# ChessMechPCB2.net
KiCad netlist of a schematic drawn in EAGLE
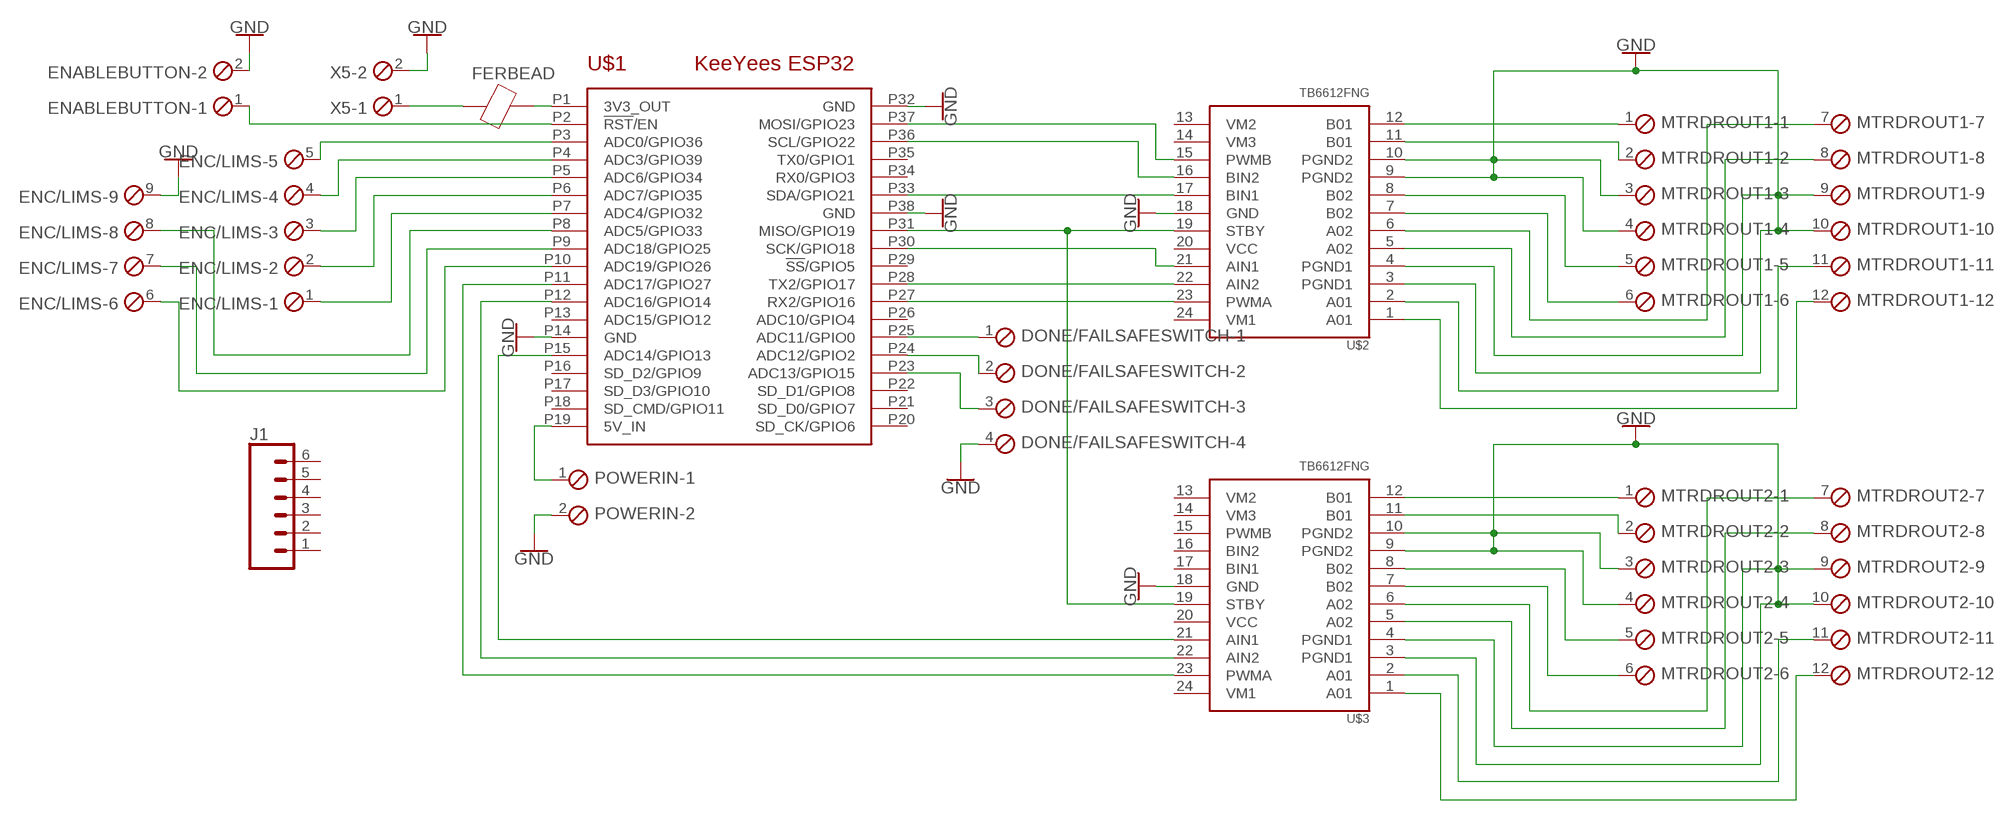
[diagram p0: schematic, sheet 1]

(export (version "E")
  (design (tool "Eeschema 10.0.6"))
  (components
    (comp (ref "DONE/FAILSAFESWITCH")
      (value "SCREWTERM_4P_254")
      (footprint "eagle-import:4POL254")
      (libsource (lib "eagle-import") (part "SCREWTERM_4P_254"))
    )
    (comp (ref "ENABLEBUTTON")
      (value "SCREWTERM_2P_254")
      (footprint "eagle-import:2POL254")
      (libsource (lib "eagle-import") (part "SCREWTERM_2P_254"))
    )
    (comp (ref "ENC/LIMS")
      (value "SCREWTERM_9P_254")
      (footprint "eagle-import:9POL254")
      (libsource (lib "eagle-import") (part "SCREWTERM_9P_254"))
    )
    (comp (ref "FERBEAD")
      (value "BEAD0402")
      (footprint "eagle-import:0402")
      (libsource (lib "eagle-import") (part "BEAD0402"))
    )
    (comp (ref "J1")
      (value "CONN_06SILK_FEMALE_PTH")
      (footprint "eagle-import:1X06")
      (libsource (lib "eagle-import") (part "CONN_06SILK_FEMALE_PTH"))
    )
    (comp (ref "MTRDROUT1")
      (value "SCREWTERM_12P_254")
      (footprint "eagle-import:12POL254")
      (libsource (lib "eagle-import") (part "SCREWTERM_12P_254"))
    )
    (comp (ref "MTRDROUT2")
      (value "SCREWTERM_12P_254")
      (footprint "eagle-import:12POL254")
      (libsource (lib "eagle-import") (part "SCREWTERM_12P_254"))
    )
    (comp (ref "POWERIN")
      (value "SCREWTERM_2P_254")
      (footprint "eagle-import:2POL254")
      (libsource (lib "eagle-import") (part "SCREWTERM_2P_254"))
    )
    (comp (ref "U$1")
      (value "KEEYEES_ESP32")
      (footprint "eagle-import:KEEYEES_ESP32")
      (libsource (lib "eagle-import") (part "KEEYEES_ESP32"))
    )
    (comp (ref "U$2")
      (value "TB6612FNG")
      (footprint "eagle-import:SSOP24")
      (libsource (lib "eagle-import") (part "TB6612FNG"))
    )
    (comp (ref "U$3")
      (value "TB6612FNG")
      (footprint "eagle-import:SSOP24")
      (libsource (lib "eagle-import") (part "TB6612FNG"))
    )
    (comp (ref "X5")
      (value "SCREWTERM_2P_254")
      (footprint "eagle-import:2POL254")
      (libsource (lib "eagle-import") (part "SCREWTERM_2P_254"))
    )
  )
  (nets
    (net (code "1") (name "GND") (class "Default")
      (node (ref "DONE/FAILSAFESWITCH") (pin "4") (pinfunction "1_4") (pintype "passive"))
      (node (ref "ENABLEBUTTON") (pin "2") (pinfunction "1_2") (pintype "passive"))
      (node (ref "ENC/LIMS") (pin "9") (pinfunction "1_9") (pintype "passive"))
      (node (ref "MTRDROUT1") (pin "10") (pinfunction "1_10") (pintype "passive"))
      (node (ref "MTRDROUT1") (pin "3") (pinfunction "1_3") (pintype "passive"))
      (node (ref "MTRDROUT1") (pin "4") (pinfunction "1_4") (pintype "passive"))
      (node (ref "MTRDROUT1") (pin "9") (pinfunction "1_9") (pintype "passive"))
      (node (ref "MTRDROUT2") (pin "10") (pinfunction "1_10") (pintype "passive"))
      (node (ref "MTRDROUT2") (pin "3") (pinfunction "1_3") (pintype "passive"))
      (node (ref "MTRDROUT2") (pin "4") (pinfunction "1_4") (pintype "passive"))
      (node (ref "MTRDROUT2") (pin "9") (pinfunction "1_9") (pintype "passive"))
      (node (ref "POWERIN") (pin "2") (pinfunction "1_2") (pintype "passive"))
      (node (ref "U$1") (pin "P14") (pinfunction "GND_P14") (pintype "power_in"))
      (node (ref "U$1") (pin "P32") (pinfunction "GND_P32") (pintype "power_in"))
      (node (ref "U$1") (pin "P38") (pinfunction "GND_P38") (pintype "power_in"))
      (node (ref "U$2") (pin "10") (pinfunction "PGND2_10") (pintype "bidirectional"))
      (node (ref "U$2") (pin "18") (pinfunction "GND_18") (pintype "bidirectional"))
      (node (ref "U$2") (pin "3") (pinfunction "PGND1_3") (pintype "bidirectional"))
      (node (ref "U$2") (pin "4") (pinfunction "PGND1_4") (pintype "bidirectional"))
      (node (ref "U$2") (pin "9") (pinfunction "PGND2_9") (pintype "bidirectional"))
      (node (ref "U$3") (pin "10") (pinfunction "PGND2_10") (pintype "bidirectional"))
      (node (ref "U$3") (pin "18") (pinfunction "GND_18") (pintype "bidirectional"))
      (node (ref "U$3") (pin "3") (pinfunction "PGND1_3") (pintype "bidirectional"))
      (node (ref "U$3") (pin "4") (pinfunction "PGND1_4") (pintype "bidirectional"))
      (node (ref "U$3") (pin "9") (pinfunction "PGND2_9") (pintype "bidirectional"))
      (node (ref "X5") (pin "2") (pinfunction "1_2") (pintype "passive"))
    )
    (net (code "2") (name "Net-(DONE/FAILSAFESWITCHB-1)") (class "Default")
      (node (ref "DONE/FAILSAFESWITCH") (pin "2") (pinfunction "1_2") (pintype "passive"))
      (node (ref "U$1") (pin "P24") (pinfunction "ADC12/GPIO2_P24") (pintype "bidirectional"))
    )
    (net (code "3") (name "Net-(DONE/FAILSAFESWITCHC-1)") (class "Default")
      (node (ref "DONE/FAILSAFESWITCH") (pin "3") (pinfunction "1_3") (pintype "passive"))
      (node (ref "U$1") (pin "P23") (pinfunction "ADC13/GPIO15_P23") (pintype "bidirectional"))
    )
    (net (code "4") (name "Net-(ENC/LIMSB-1)") (class "Default")
      (node (ref "ENC/LIMS") (pin "2") (pinfunction "1_2") (pintype "passive"))
      (node (ref "U$1") (pin "P6") (pinfunction "ADC7/GPIO35_P6") (pintype "bidirectional"))
    )
    (net (code "5") (name "Net-(ENC/LIMSC-1)") (class "Default")
      (node (ref "ENC/LIMS") (pin "3") (pinfunction "1_3") (pintype "passive"))
      (node (ref "U$1") (pin "P5") (pinfunction "ADC6/GPIO34_P5") (pintype "bidirectional"))
    )
    (net (code "6") (name "Net-(ENC/LIMSD-1)") (class "Default")
      (node (ref "ENC/LIMS") (pin "4") (pinfunction "1_4") (pintype "passive"))
      (node (ref "U$1") (pin "P4") (pinfunction "ADC3/GPIO39_P4") (pintype "bidirectional"))
    )
    (net (code "7") (name "Net-(ENC/LIMSE-1)") (class "Default")
      (node (ref "ENC/LIMS") (pin "5") (pinfunction "1_5") (pintype "passive"))
      (node (ref "U$1") (pin "P3") (pinfunction "ADC0/GPIO36_P3") (pintype "bidirectional"))
    )
    (net (code "8") (name "Net-(ENC/LIMSF-1)") (class "Default")
      (node (ref "ENC/LIMS") (pin "6") (pinfunction "1_6") (pintype "passive"))
      (node (ref "U$1") (pin "P10") (pinfunction "ADC19/GPIO26_P10") (pintype "bidirectional"))
    )
    (net (code "9") (name "Net-(ENC/LIMSG-1)") (class "Default")
      (node (ref "ENC/LIMS") (pin "7") (pinfunction "1_7") (pintype "passive"))
      (node (ref "U$1") (pin "P9") (pinfunction "ADC18/GPIO25_P9") (pintype "bidirectional"))
    )
    (net (code "10") (name "Net-(ENC/LIMSH-1)") (class "Default")
      (node (ref "ENC/LIMS") (pin "8") (pinfunction "1_8") (pintype "passive"))
      (node (ref "U$1") (pin "P8") (pinfunction "ADC5/GPIO33_P8") (pintype "bidirectional"))
    )
    (net (code "11") (name "Net-(FERBEAD-Pad1)") (class "Default")
      (node (ref "FERBEAD") (pin "1") (pinfunction "1_1") (pintype "bidirectional"))
      (node (ref "X5") (pin "1") (pinfunction "1_1") (pintype "passive"))
    )
    (net (code "12") (name "Net-(MTRDROUT1-Pad1)") (class "Default")
      (node (ref "MTRDROUT1") (pin "1") (pinfunction "1_1") (pintype "passive"))
      (node (ref "U$2") (pin "12") (pinfunction "B01_12") (pintype "bidirectional"))
    )
    (net (code "13") (name "Net-(MTRDROUT1C-1)") (class "Default")
      (node (ref "MTRDROUT1") (pin "11") (pinfunction "1_11") (pintype "passive"))
      (node (ref "U$2") (pin "2") (pinfunction "A01_2") (pintype "bidirectional"))
    )
    (net (code "14") (name "Net-(MTRDROUT1D-1)") (class "Default")
      (node (ref "MTRDROUT1") (pin "12") (pinfunction "1_12") (pintype "passive"))
      (node (ref "U$2") (pin "1") (pinfunction "A01_1") (pintype "bidirectional"))
    )
    (net (code "15") (name "Net-(MTRDROUT1E-1)") (class "Default")
      (node (ref "MTRDROUT1") (pin "2") (pinfunction "1_2") (pintype "passive"))
      (node (ref "U$2") (pin "11") (pinfunction "B01_11") (pintype "bidirectional"))
    )
    (net (code "16") (name "Net-(MTRDROUT1H-1)") (class "Default")
      (node (ref "MTRDROUT1") (pin "5") (pinfunction "1_5") (pintype "passive"))
      (node (ref "U$2") (pin "8") (pinfunction "B02_8") (pintype "bidirectional"))
    )
    (net (code "17") (name "Net-(MTRDROUT1I-1)") (class "Default")
      (node (ref "MTRDROUT1") (pin "6") (pinfunction "1_6") (pintype "passive"))
      (node (ref "U$2") (pin "7") (pinfunction "B02_7") (pintype "bidirectional"))
    )
    (net (code "18") (name "Net-(MTRDROUT1J-1)") (class "Default")
      (node (ref "MTRDROUT1") (pin "7") (pinfunction "1_7") (pintype "passive"))
      (node (ref "U$2") (pin "6") (pinfunction "A02_6") (pintype "bidirectional"))
    )
    (net (code "19") (name "Net-(MTRDROUT1K-1)") (class "Default")
      (node (ref "MTRDROUT1") (pin "8") (pinfunction "1_8") (pintype "passive"))
      (node (ref "U$2") (pin "5") (pinfunction "A02_5") (pintype "bidirectional"))
    )
    (net (code "20") (name "Net-(MTRDROUT2-Pad1)") (class "Default")
      (node (ref "MTRDROUT2") (pin "1") (pinfunction "1_1") (pintype "passive"))
      (node (ref "U$3") (pin "12") (pinfunction "B01_12") (pintype "bidirectional"))
    )
    (net (code "21") (name "Net-(MTRDROUT2C-1)") (class "Default")
      (node (ref "MTRDROUT2") (pin "11") (pinfunction "1_11") (pintype "passive"))
      (node (ref "U$3") (pin "2") (pinfunction "A01_2") (pintype "bidirectional"))
    )
    (net (code "22") (name "Net-(MTRDROUT2D-1)") (class "Default")
      (node (ref "MTRDROUT2") (pin "12") (pinfunction "1_12") (pintype "passive"))
      (node (ref "U$3") (pin "1") (pinfunction "A01_1") (pintype "bidirectional"))
    )
    (net (code "23") (name "Net-(MTRDROUT2E-1)") (class "Default")
      (node (ref "MTRDROUT2") (pin "2") (pinfunction "1_2") (pintype "passive"))
      (node (ref "U$3") (pin "11") (pinfunction "B01_11") (pintype "bidirectional"))
    )
    (net (code "24") (name "Net-(MTRDROUT2H-1)") (class "Default")
      (node (ref "MTRDROUT2") (pin "5") (pinfunction "1_5") (pintype "passive"))
      (node (ref "U$3") (pin "8") (pinfunction "B02_8") (pintype "bidirectional"))
    )
    (net (code "25") (name "Net-(MTRDROUT2I-1)") (class "Default")
      (node (ref "MTRDROUT2") (pin "6") (pinfunction "1_6") (pintype "passive"))
      (node (ref "U$3") (pin "7") (pinfunction "B02_7") (pintype "bidirectional"))
    )
    (net (code "26") (name "Net-(MTRDROUT2J-1)") (class "Default")
      (node (ref "MTRDROUT2") (pin "7") (pinfunction "1_7") (pintype "passive"))
      (node (ref "U$3") (pin "6") (pinfunction "A02_6") (pintype "bidirectional"))
    )
    (net (code "27") (name "Net-(MTRDROUT2K-1)") (class "Default")
      (node (ref "MTRDROUT2") (pin "8") (pinfunction "1_8") (pintype "passive"))
      (node (ref "U$3") (pin "5") (pinfunction "A02_5") (pintype "bidirectional"))
    )
    (net (code "28") (name "Net-(U$1-3V3_OUT)") (class "Default")
      (node (ref "FERBEAD") (pin "2") (pinfunction "2_2") (pintype "bidirectional"))
      (node (ref "U$1") (pin "P1") (pinfunction "3V3_OUT_P1") (pintype "power_in"))
    )
    (net (code "29") (name "Net-(U$1-5V_IN)") (class "Default")
      (node (ref "POWERIN") (pin "1") (pinfunction "1_1") (pintype "passive"))
      (node (ref "U$1") (pin "P19") (pinfunction "5V_IN_P19") (pintype "power_in"))
    )
    (net (code "30") (name "Net-(U$1-ADC4{slash}GPIO32)") (class "Default")
      (node (ref "ENC/LIMS") (pin "1") (pinfunction "1_1") (pintype "passive"))
      (node (ref "U$1") (pin "P7") (pinfunction "ADC4/GPIO32_P7") (pintype "bidirectional"))
    )
    (net (code "31") (name "Net-(U$1-ADC11{slash}GPIO0)") (class "Default")
      (node (ref "DONE/FAILSAFESWITCH") (pin "1") (pinfunction "1_1") (pintype "passive"))
      (node (ref "U$1") (pin "P25") (pinfunction "ADC11/GPIO0_P25") (pintype "bidirectional"))
    )
    (net (code "32") (name "Net-(U$1-ADC14{slash}GPIO13)") (class "Default")
      (node (ref "U$1") (pin "P15") (pinfunction "ADC14/GPIO13_P15") (pintype "bidirectional"))
      (node (ref "U$3") (pin "21") (pinfunction "AIN1_21") (pintype "bidirectional"))
    )
    (net (code "33") (name "Net-(U$1-ADC16{slash}GPIO14)") (class "Default")
      (node (ref "U$1") (pin "P12") (pinfunction "ADC16/GPIO14_P12") (pintype "bidirectional"))
      (node (ref "U$3") (pin "22") (pinfunction "AIN2_22") (pintype "bidirectional"))
    )
    (net (code "34") (name "Net-(U$1-ADC17{slash}GPIO27)") (class "Default")
      (node (ref "U$1") (pin "P11") (pinfunction "ADC17/GPIO27_P11") (pintype "bidirectional"))
      (node (ref "U$3") (pin "23") (pinfunction "PWMA_23") (pintype "bidirectional"))
    )
    (net (code "35") (name "Net-(U$1-MISO{slash}GPIO19)") (class "Default")
      (node (ref "U$1") (pin "P31") (pinfunction "MISO/GPIO19_P31") (pintype "bidirectional"))
      (node (ref "U$2") (pin "19") (pinfunction "STBY_19") (pintype "bidirectional"))
      (node (ref "U$3") (pin "19") (pinfunction "STBY_19") (pintype "bidirectional"))
    )
    (net (code "36") (name "Net-(U$1-MOSI{slash}GPIO23)") (class "Default")
      (node (ref "U$1") (pin "P37") (pinfunction "MOSI/GPIO23_P37") (pintype "bidirectional"))
      (node (ref "U$2") (pin "15") (pinfunction "PWMB_15") (pintype "bidirectional"))
    )
    (net (code "37") (name "Net-(U$1-RX2{slash}GPIO16)") (class "Default")
      (node (ref "U$1") (pin "P27") (pinfunction "RX2/GPIO16_P27") (pintype "bidirectional"))
      (node (ref "U$2") (pin "23") (pinfunction "PWMA_23") (pintype "bidirectional"))
    )
    (net (code "38") (name "Net-(U$1-SCK{slash}GPIO18)") (class "Default")
      (node (ref "U$1") (pin "P30") (pinfunction "SCK/GPIO18_P30") (pintype "bidirectional"))
      (node (ref "U$2") (pin "21") (pinfunction "AIN1_21") (pintype "bidirectional"))
    )
    (net (code "39") (name "Net-(U$1-SCL{slash}GPIO22)") (class "Default")
      (node (ref "U$1") (pin "P36") (pinfunction "SCL/GPIO22_P36") (pintype "bidirectional"))
      (node (ref "U$2") (pin "16") (pinfunction "BIN2_16") (pintype "bidirectional"))
    )
    (net (code "40") (name "Net-(U$1-SDA{slash}GPIO21)") (class "Default")
      (node (ref "U$1") (pin "P33") (pinfunction "SDA/GPIO21_P33") (pintype "bidirectional"))
      (node (ref "U$2") (pin "17") (pinfunction "BIN1_17") (pintype "bidirectional"))
    )
    (net (code "41") (name "Net-(U$1-TX2{slash}GPIO17)") (class "Default")
      (node (ref "U$1") (pin "P28") (pinfunction "TX2/GPIO17_P28") (pintype "bidirectional"))
      (node (ref "U$2") (pin "22") (pinfunction "AIN2_22") (pintype "bidirectional"))
    )
    (net (code "42") (name "Net-(U$1-~{RST}{slash}EN)") (class "Default")
      (node (ref "ENABLEBUTTON") (pin "1") (pinfunction "1_1") (pintype "passive"))
      (node (ref "U$1") (pin "P2") (pinfunction "~{RST}/EN_P2") (pintype "input"))
    )
    (net (code "43") (name "unconnected-(J1-Pad1)") (class "Default")
      (node (ref "J1") (pin "1") (pinfunction "1_1") (pintype "passive"))
    )
    (net (code "44") (name "unconnected-(J1-Pad2)") (class "Default")
      (node (ref "J1") (pin "2") (pinfunction "2_2") (pintype "passive"))
    )
    (net (code "45") (name "unconnected-(J1-Pad3)") (class "Default")
      (node (ref "J1") (pin "3") (pinfunction "3_3") (pintype "passive"))
    )
    (net (code "46") (name "unconnected-(J1-Pad4)") (class "Default")
      (node (ref "J1") (pin "4") (pinfunction "4_4") (pintype "passive"))
    )
    (net (code "47") (name "unconnected-(J1-Pad5)") (class "Default")
      (node (ref "J1") (pin "5") (pinfunction "5_5") (pintype "passive"))
    )
    (net (code "48") (name "unconnected-(J1-Pad6)") (class "Default")
      (node (ref "J1") (pin "6") (pinfunction "6_6") (pintype "passive"))
    )
    (net (code "49") (name "unconnected-(U$1-ADC10{slash}GPIO4-PadP26)") (class "Default")
      (node (ref "U$1") (pin "P26") (pinfunction "ADC10/GPIO4_P26") (pintype "bidirectional"))
    )
    (net (code "50") (name "unconnected-(U$1-ADC15{slash}GPIO12-PadP13)") (class "Default")
      (node (ref "U$1") (pin "P13") (pinfunction "ADC15/GPIO12_P13") (pintype "bidirectional"))
    )
    (net (code "51") (name "unconnected-(U$1-RX0{slash}GPIO3-PadP34)") (class "Default")
      (node (ref "U$1") (pin "P34") (pinfunction "RX0/GPIO3_P34") (pintype "bidirectional"))
    )
    (net (code "52") (name "unconnected-(U$1-SD_CK{slash}GPIO6-PadP20)") (class "Default")
      (node (ref "U$1") (pin "P20") (pinfunction "SD_CK/GPIO6_P20") (pintype "bidirectional"))
    )
    (net (code "53") (name "unconnected-(U$1-SD_CMD{slash}GPIO11-PadP18)") (class "Default")
      (node (ref "U$1") (pin "P18") (pinfunction "SD_CMD/GPIO11_P18") (pintype "bidirectional"))
    )
    (net (code "54") (name "unconnected-(U$1-SD_D0{slash}GPIO7-PadP21)") (class "Default")
      (node (ref "U$1") (pin "P21") (pinfunction "SD_D0/GPIO7_P21") (pintype "bidirectional"))
    )
    (net (code "55") (name "unconnected-(U$1-SD_D1{slash}GPIO8-PadP22)") (class "Default")
      (node (ref "U$1") (pin "P22") (pinfunction "SD_D1/GPIO8_P22") (pintype "bidirectional"))
    )
    (net (code "56") (name "unconnected-(U$1-SD_D2{slash}GPIO9-PadP16)") (class "Default")
      (node (ref "U$1") (pin "P16") (pinfunction "SD_D2/GPIO9_P16") (pintype "bidirectional"))
    )
    (net (code "57") (name "unconnected-(U$1-SD_D3{slash}GPIO10-PadP17)") (class "Default")
      (node (ref "U$1") (pin "P17") (pinfunction "SD_D3/GPIO10_P17") (pintype "bidirectional"))
    )
    (net (code "58") (name "unconnected-(U$1-TX0{slash}GPIO1-PadP35)") (class "Default")
      (node (ref "U$1") (pin "P35") (pinfunction "TX0/GPIO1_P35") (pintype "bidirectional"))
    )
    (net (code "59") (name "unconnected-(U$1-~{SS}{slash}GPIO5-PadP29)") (class "Default")
      (node (ref "U$1") (pin "P29") (pinfunction "~{SS}/GPIO5_P29") (pintype "bidirectional"))
    )
    (net (code "60") (name "unconnected-(U$2-VCC-Pad20)") (class "Default")
      (node (ref "U$2") (pin "20") (pinfunction "VCC_20") (pintype "bidirectional"))
    )
    (net (code "61") (name "unconnected-(U$2-VM1-Pad24)") (class "Default")
      (node (ref "U$2") (pin "24") (pinfunction "VM1_24") (pintype "bidirectional"))
    )
    (net (code "62") (name "unconnected-(U$2-VM2-Pad13)") (class "Default")
      (node (ref "U$2") (pin "13") (pinfunction "VM2_13") (pintype "bidirectional"))
    )
    (net (code "63") (name "unconnected-(U$2-VM3-Pad14)") (class "Default")
      (node (ref "U$2") (pin "14") (pinfunction "VM3_14") (pintype "bidirectional"))
    )
    (net (code "64") (name "unconnected-(U$3-BIN1-Pad17)") (class "Default")
      (node (ref "U$3") (pin "17") (pinfunction "BIN1_17") (pintype "bidirectional"))
    )
    (net (code "65") (name "unconnected-(U$3-BIN2-Pad16)") (class "Default")
      (node (ref "U$3") (pin "16") (pinfunction "BIN2_16") (pintype "bidirectional"))
    )
    (net (code "66") (name "unconnected-(U$3-PWMB-Pad15)") (class "Default")
      (node (ref "U$3") (pin "15") (pinfunction "PWMB_15") (pintype "bidirectional"))
    )
    (net (code "67") (name "unconnected-(U$3-VCC-Pad20)") (class "Default")
      (node (ref "U$3") (pin "20") (pinfunction "VCC_20") (pintype "bidirectional"))
    )
    (net (code "68") (name "unconnected-(U$3-VM1-Pad24)") (class "Default")
      (node (ref "U$3") (pin "24") (pinfunction "VM1_24") (pintype "bidirectional"))
    )
    (net (code "69") (name "unconnected-(U$3-VM2-Pad13)") (class "Default")
      (node (ref "U$3") (pin "13") (pinfunction "VM2_13") (pintype "bidirectional"))
    )
    (net (code "70") (name "unconnected-(U$3-VM3-Pad14)") (class "Default")
      (node (ref "U$3") (pin "14") (pinfunction "VM3_14") (pintype "bidirectional"))
    )
  )
)
